# asserv.net
KiCad netlist of a schematic drawn in EAGLE
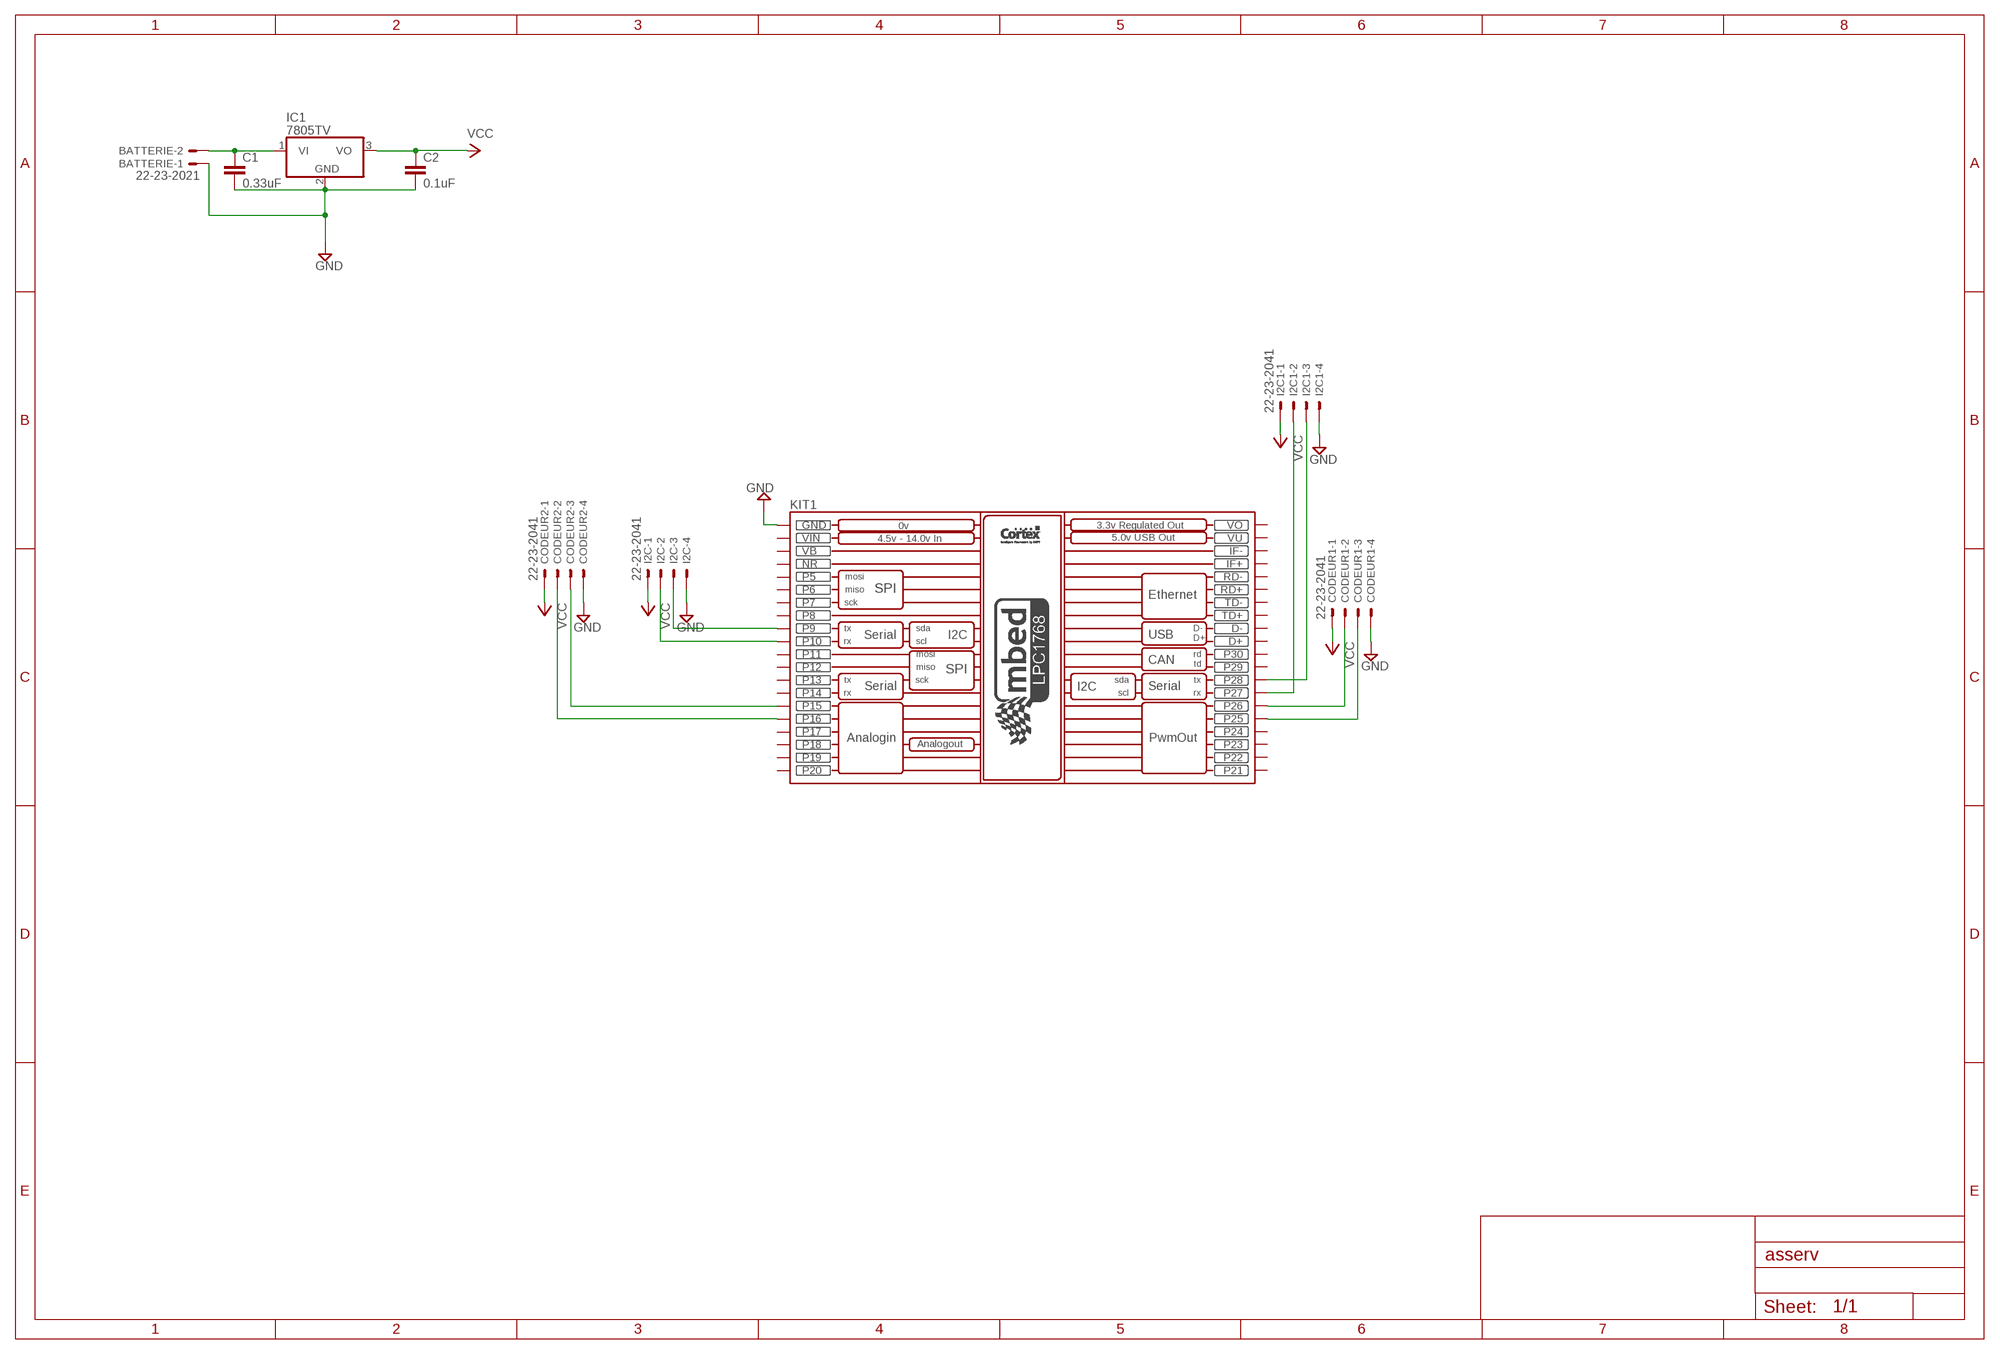
[diagram p0: schematic, sheet 1]

(export (version "E")
  (design (tool "Eeschema 10.0.6"))
  (components
    (comp (ref "BATTERIE")
      (value "22-23-2021")
      (footprint "eagle-import:22-23-2021")
      (fields (field (name "MF") "MOLEX"))
      (libsource (lib "eagle-import") (part "22-23-2021"))
    )
    (comp (ref "C1")
      (value "0.33uF")
      (footprint "eagle-import:C5B2.5")
      (libsource (lib "eagle-import") (part "C5/2.5"))
    )
    (comp (ref "C2")
      (value "0.1uF")
      (footprint "eagle-import:C5B2.5")
      (libsource (lib "eagle-import") (part "C5/2.5"))
    )
    (comp (ref "CODEUR1")
      (value "22-23-2041")
      (footprint "eagle-import:22-23-2041")
      (fields (field (name "MF") "MOLEX"))
      (libsource (lib "eagle-import") (part "22-23-2041"))
    )
    (comp (ref "CODEUR2")
      (value "22-23-2041")
      (footprint "eagle-import:22-23-2041")
      (fields (field (name "MF") "MOLEX"))
      (libsource (lib "eagle-import") (part "22-23-2041"))
    )
    (comp (ref "I2C")
      (value "22-23-2041")
      (footprint "eagle-import:22-23-2041")
      (fields (field (name "MF") "MOLEX"))
      (libsource (lib "eagle-import") (part "22-23-2041"))
    )
    (comp (ref "I2C1")
      (value "22-23-2041")
      (footprint "eagle-import:22-23-2041")
      (fields (field (name "MF") "MOLEX"))
      (libsource (lib "eagle-import") (part "22-23-2041"))
    )
    (comp (ref "IC1")
      (value "7805TV")
      (footprint "eagle-import:TO220V")
      (libsource (lib "eagle-import") (part "78TV05"))
    )
    (comp (ref "KIT1")
      (value "MBED_NXP_LPC1768")
      (footprint "eagle-import:MBED-KIT")
      (libsource (lib "eagle-import") (part "MBED_NXP_LPC1768"))
    )
  )
  (nets
    (net (code "1") (name "/NR") (class "Default")
      (node (ref "KIT1") (pin "NR") (pinfunction "NR_NR") (pintype "power_in"))
    )
    (net (code "2") (name "/VB") (class "Default")
      (node (ref "KIT1") (pin "VB") (pinfunction "VB_VB") (pintype "power_in"))
    )
    (net (code "3") (name "/VIN") (class "Default")
      (node (ref "KIT1") (pin "VIN") (pinfunction "VIN_VIN") (pintype "power_in"))
    )
    (net (code "4") (name "/VO") (class "Default")
      (node (ref "KIT1") (pin "VOUT") (pinfunction "VO_VOUT") (pintype "power_in"))
    )
    (net (code "5") (name "/VU") (class "Default")
      (node (ref "KIT1") (pin "VU") (pinfunction "VU_VU") (pintype "power_in"))
    )
    (net (code "6") (name "GND") (class "Default")
      (node (ref "BATTERIE") (pin "1") (pinfunction "S_1") (pintype "passive"))
      (node (ref "C1") (pin "2") (pinfunction "2_2") (pintype "passive"))
      (node (ref "C2") (pin "2") (pinfunction "2_2") (pintype "passive"))
      (node (ref "CODEUR1") (pin "4") (pinfunction "S_4") (pintype "passive"))
      (node (ref "CODEUR2") (pin "4") (pinfunction "S_4") (pintype "passive"))
      (node (ref "I2C") (pin "4") (pinfunction "S_4") (pintype "passive"))
      (node (ref "I2C1") (pin "4") (pinfunction "S_4") (pintype "passive"))
      (node (ref "IC1") (pin "2") (pinfunction "GND_2") (pintype "passive"))
      (node (ref "KIT1") (pin "GND") (pinfunction "GND_GND") (pintype "power_in"))
    )
    (net (code "7") (name "Net-(BATTERIEB-S)") (class "Default")
      (node (ref "BATTERIE") (pin "2") (pinfunction "S_2") (pintype "passive"))
      (node (ref "C1") (pin "1") (pinfunction "1_1") (pintype "passive"))
      (node (ref "IC1") (pin "1") (pinfunction "VI_1") (pintype "input"))
    )
    (net (code "8") (name "Net-(CODEUR1B-S)") (class "Default")
      (node (ref "CODEUR1") (pin "2") (pinfunction "S_2") (pintype "passive"))
      (node (ref "KIT1") (pin "P$26") (pinfunction "P26_P$26") (pintype "bidirectional"))
    )
    (net (code "9") (name "Net-(CODEUR1C-S)") (class "Default")
      (node (ref "CODEUR1") (pin "3") (pinfunction "S_3") (pintype "passive"))
      (node (ref "KIT1") (pin "P$25") (pinfunction "P25_P$25") (pintype "bidirectional"))
    )
    (net (code "10") (name "Net-(CODEUR2B-S)") (class "Default")
      (node (ref "CODEUR2") (pin "2") (pinfunction "S_2") (pintype "passive"))
      (node (ref "KIT1") (pin "P$16") (pinfunction "P16_P$16") (pintype "bidirectional"))
    )
    (net (code "11") (name "Net-(CODEUR2C-S)") (class "Default")
      (node (ref "CODEUR2") (pin "3") (pinfunction "S_3") (pintype "passive"))
      (node (ref "KIT1") (pin "P$15") (pinfunction "P15_P$15") (pintype "bidirectional"))
    )
    (net (code "12") (name "Net-(I2C1B-S)") (class "Default")
      (node (ref "I2C1") (pin "2") (pinfunction "S_2") (pintype "passive"))
      (node (ref "KIT1") (pin "P$27") (pinfunction "P27_P$27") (pintype "bidirectional"))
    )
    (net (code "13") (name "Net-(I2C1C-S)") (class "Default")
      (node (ref "I2C1") (pin "3") (pinfunction "S_3") (pintype "passive"))
      (node (ref "KIT1") (pin "P$28") (pinfunction "P28_P$28") (pintype "bidirectional"))
    )
    (net (code "14") (name "Net-(I2CB-S)") (class "Default")
      (node (ref "I2C") (pin "2") (pinfunction "S_2") (pintype "passive"))
      (node (ref "KIT1") (pin "P$10") (pinfunction "P10_P$10") (pintype "bidirectional"))
    )
    (net (code "15") (name "Net-(I2CC-S)") (class "Default")
      (node (ref "I2C") (pin "3") (pinfunction "S_3") (pintype "passive"))
      (node (ref "KIT1") (pin "P$9") (pinfunction "P9_P$9") (pintype "bidirectional"))
    )
    (net (code "16") (name "VCC") (class "Default")
      (node (ref "C2") (pin "1") (pinfunction "1_1") (pintype "passive"))
      (node (ref "CODEUR1") (pin "1") (pinfunction "S_1") (pintype "passive"))
      (node (ref "CODEUR2") (pin "1") (pinfunction "S_1") (pintype "passive"))
      (node (ref "I2C") (pin "1") (pinfunction "S_1") (pintype "passive"))
      (node (ref "I2C1") (pin "1") (pinfunction "S_1") (pintype "passive"))
      (node (ref "IC1") (pin "3") (pinfunction "VO_3") (pintype "passive"))
    )
    (net (code "17") (name "unconnected-(KIT1-P5-PadP$5)") (class "Default")
      (node (ref "KIT1") (pin "P$5") (pinfunction "P5_P$5") (pintype "bidirectional"))
    )
    (net (code "18") (name "unconnected-(KIT1-P6-PadP$6)") (class "Default")
      (node (ref "KIT1") (pin "P$6") (pinfunction "P6_P$6") (pintype "bidirectional"))
    )
    (net (code "19") (name "unconnected-(KIT1-P7-PadP$7)") (class "Default")
      (node (ref "KIT1") (pin "P$7") (pinfunction "P7_P$7") (pintype "bidirectional"))
    )
    (net (code "20") (name "unconnected-(KIT1-P8-PadP$8)") (class "Default")
      (node (ref "KIT1") (pin "P$8") (pinfunction "P8_P$8") (pintype "bidirectional"))
    )
    (net (code "21") (name "unconnected-(KIT1-P11-PadP$11)") (class "Default")
      (node (ref "KIT1") (pin "P$11") (pinfunction "P11_P$11") (pintype "bidirectional"))
    )
    (net (code "22") (name "unconnected-(KIT1-P12-PadP$12)") (class "Default")
      (node (ref "KIT1") (pin "P$12") (pinfunction "P12_P$12") (pintype "bidirectional"))
    )
    (net (code "23") (name "unconnected-(KIT1-P13-PadP$13)") (class "Default")
      (node (ref "KIT1") (pin "P$13") (pinfunction "P13_P$13") (pintype "bidirectional"))
    )
    (net (code "24") (name "unconnected-(KIT1-P14-PadP$14)") (class "Default")
      (node (ref "KIT1") (pin "P$14") (pinfunction "P14_P$14") (pintype "bidirectional"))
    )
    (net (code "25") (name "unconnected-(KIT1-P17-PadP$17)") (class "Default")
      (node (ref "KIT1") (pin "P$17") (pinfunction "P17_P$17") (pintype "bidirectional"))
    )
    (net (code "26") (name "unconnected-(KIT1-P18-PadP$18)") (class "Default")
      (node (ref "KIT1") (pin "P$18") (pinfunction "P18_P$18") (pintype "bidirectional"))
    )
    (net (code "27") (name "unconnected-(KIT1-P19-PadP$19)") (class "Default")
      (node (ref "KIT1") (pin "P$19") (pinfunction "P19_P$19") (pintype "bidirectional"))
    )
    (net (code "28") (name "unconnected-(KIT1-P20-PadP$20)") (class "Default")
      (node (ref "KIT1") (pin "P$20") (pinfunction "P20_P$20") (pintype "bidirectional"))
    )
    (net (code "29") (name "unconnected-(KIT1-P21-PadP$21)") (class "Default")
      (node (ref "KIT1") (pin "P$21") (pinfunction "P21_P$21") (pintype "bidirectional"))
    )
    (net (code "30") (name "unconnected-(KIT1-P22-PadP$22)") (class "Default")
      (node (ref "KIT1") (pin "P$22") (pinfunction "P22_P$22") (pintype "bidirectional"))
    )
    (net (code "31") (name "unconnected-(KIT1-P23-PadP$23)") (class "Default")
      (node (ref "KIT1") (pin "P$23") (pinfunction "P23_P$23") (pintype "bidirectional"))
    )
    (net (code "32") (name "unconnected-(KIT1-P24-PadP$24)") (class "Default")
      (node (ref "KIT1") (pin "P$24") (pinfunction "P24_P$24") (pintype "bidirectional"))
    )
    (net (code "33") (name "unconnected-(KIT1-P29-PadP$29)") (class "Default")
      (node (ref "KIT1") (pin "P$29") (pinfunction "P29_P$29") (pintype "bidirectional"))
    )
    (net (code "34") (name "unconnected-(KIT1-P30-PadP$30)") (class "Default")
      (node (ref "KIT1") (pin "P$30") (pinfunction "P30_P$30") (pintype "bidirectional"))
    )
    (net (code "35") (name "unconnected-(KIT1-PadD+)") (class "Default")
      (node (ref "KIT1") (pin "D+") (pinfunction "D+_D+") (pintype "bidirectional"))
    )
    (net (code "36") (name "unconnected-(KIT1-PadD-)") (class "Default")
      (node (ref "KIT1") (pin "D-") (pinfunction "D-_D-") (pintype "bidirectional"))
    )
    (net (code "37") (name "unconnected-(KIT1-PadIF+)") (class "Default")
      (node (ref "KIT1") (pin "IF+") (pinfunction "IF+_IF+") (pintype "bidirectional"))
    )
    (net (code "38") (name "unconnected-(KIT1-PadIF-)") (class "Default")
      (node (ref "KIT1") (pin "IF-") (pinfunction "IF-_IF-") (pintype "bidirectional"))
    )
    (net (code "39") (name "unconnected-(KIT1-PadRD+)") (class "Default")
      (node (ref "KIT1") (pin "RD+") (pinfunction "RD+_RD+") (pintype "bidirectional"))
    )
    (net (code "40") (name "unconnected-(KIT1-PadRD-)") (class "Default")
      (node (ref "KIT1") (pin "RD-") (pinfunction "RD-_RD-") (pintype "bidirectional"))
    )
    (net (code "41") (name "unconnected-(KIT1-PadTD+)") (class "Default")
      (node (ref "KIT1") (pin "TD+") (pinfunction "TD+_TD+") (pintype "bidirectional"))
    )
    (net (code "42") (name "unconnected-(KIT1-PadTD-)") (class "Default")
      (node (ref "KIT1") (pin "TD-") (pinfunction "TD-_TD-") (pintype "bidirectional"))
    )
  )
)
